# PARKPCB.net
KiCad netlist of a schematic drawn in EAGLE
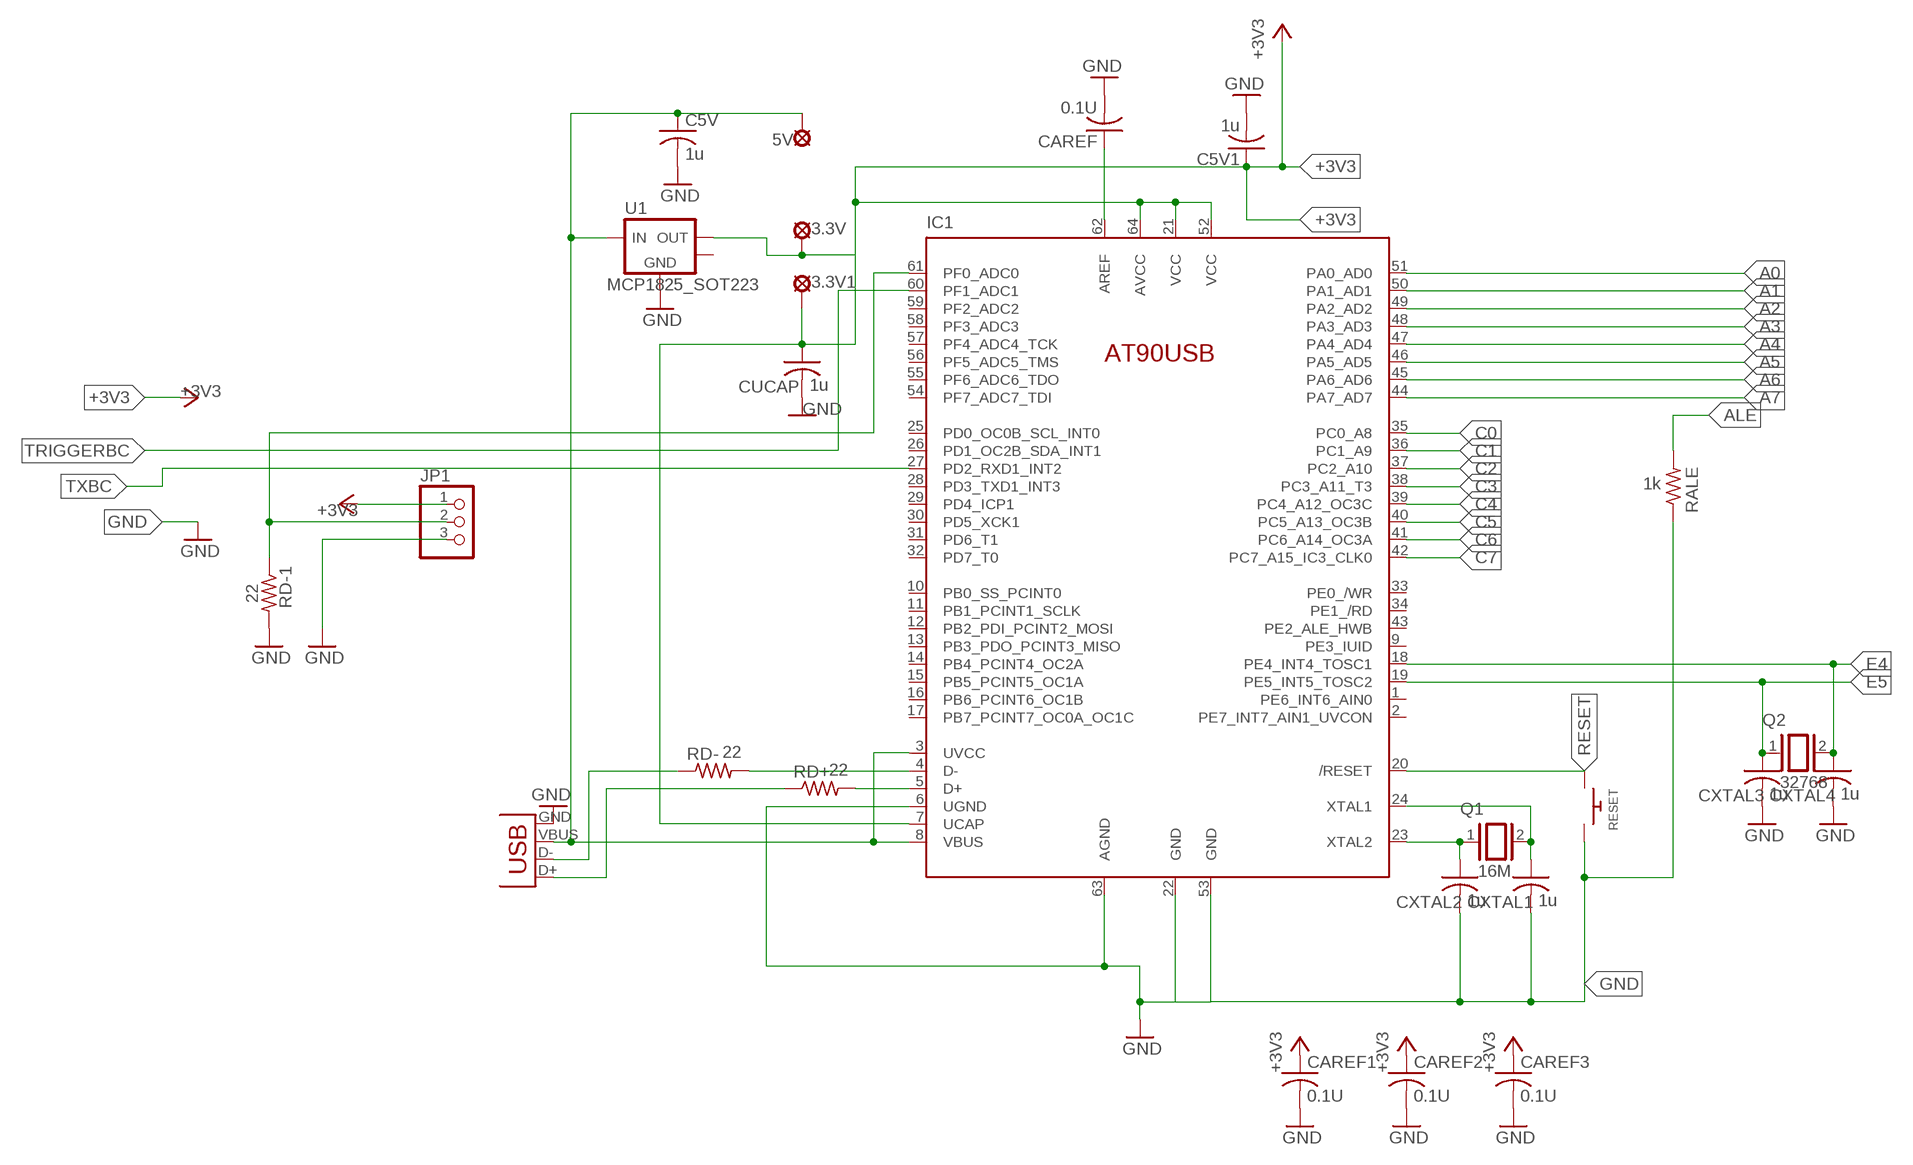
[diagram p0: schematic, sheet 1, part 1 of 2]
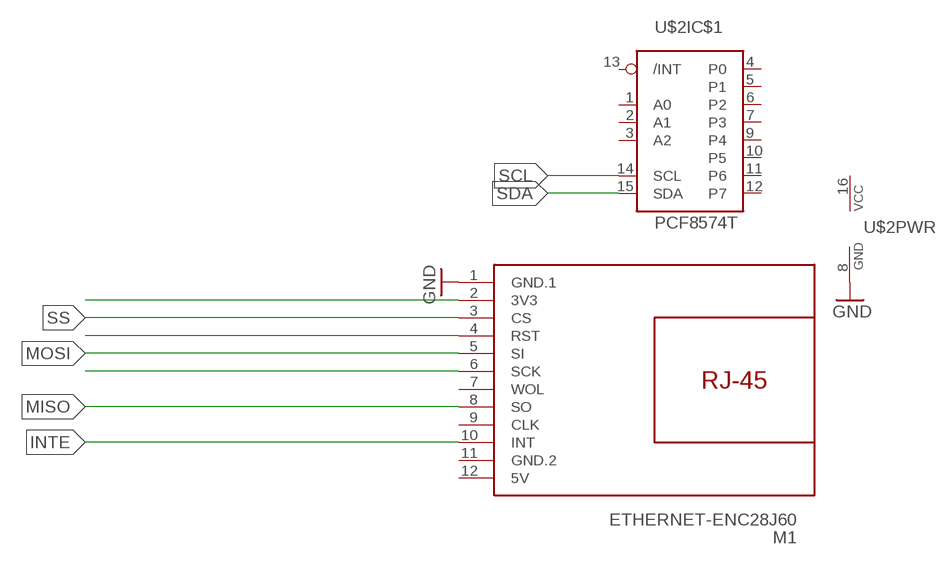
[diagram p1: schematic, sheet 1, part 2 of 2]

(export (version "E")
  (design (tool "Eeschema 10.0.6"))
  (components
    (comp (ref "3.3V")
      (value "LSP10")
      (footprint "eagle-import:LSP10")
      (libsource (lib "eagle-import") (part "LSP10"))
    )
    (comp (ref "3.3V1")
      (value "LSP10")
      (footprint "eagle-import:LSP10")
      (libsource (lib "eagle-import") (part "LSP10"))
    )
    (comp (ref "5V")
      (value "LSP10")
      (footprint "eagle-import:LSP10")
      (libsource (lib "eagle-import") (part "LSP10"))
    )
    (comp (ref "C5V")
      (value "1u")
      (footprint "eagle-import:C050-030X075")
      (libsource (lib "eagle-import") (part "C-US050-030X075"))
    )
    (comp (ref "C5V1")
      (value "1u")
      (footprint "eagle-import:C050-030X075")
      (libsource (lib "eagle-import") (part "C-US050-030X075"))
    )
    (comp (ref "CAREF")
      (value "0.1U")
      (footprint "eagle-import:C050-030X075")
      (libsource (lib "eagle-import") (part "C-US050-030X075"))
    )
    (comp (ref "CAREF1")
      (value "0.1U")
      (footprint "eagle-import:C050-030X075")
      (libsource (lib "eagle-import") (part "C-US050-030X075"))
    )
    (comp (ref "CAREF2")
      (value "0.1U")
      (footprint "eagle-import:C050-030X075")
      (libsource (lib "eagle-import") (part "C-US050-030X075"))
    )
    (comp (ref "CAREF3")
      (value "0.1U")
      (footprint "eagle-import:C050-030X075")
      (libsource (lib "eagle-import") (part "C-US050-030X075"))
    )
    (comp (ref "CUCAP")
      (value "1u")
      (footprint "eagle-import:C050-030X075")
      (libsource (lib "eagle-import") (part "C-US050-030X075"))
    )
    (comp (ref "CXTAL1")
      (value "1u")
      (footprint "eagle-import:C050-030X075")
      (libsource (lib "eagle-import") (part "C-US050-030X075"))
    )
    (comp (ref "CXTAL2")
      (value "1u")
      (footprint "eagle-import:C050-030X075")
      (libsource (lib "eagle-import") (part "C-US050-030X075"))
    )
    (comp (ref "CXTAL3")
      (value "1u")
      (footprint "eagle-import:C050-030X075")
      (libsource (lib "eagle-import") (part "C-US050-030X075"))
    )
    (comp (ref "CXTAL4")
      (value "1u")
      (footprint "eagle-import:C050-030X075")
      (libsource (lib "eagle-import") (part "C-US050-030X075"))
    )
    (comp (ref "IC1")
      (value "AT90USB-TQFP")
      (footprint "eagle-import:TQFP64")
      (libsource (lib "eagle-import") (part "AT90USB-TQFP"))
    )
    (comp (ref "JP1")
      (value "PINHD-1X3")
      (footprint "eagle-import:1X03")
      (libsource (lib "eagle-import") (part "PINHD-1X3"))
    )
    (comp (ref "M1")
      (value "ETHERNET-ENC28J60")
      (footprint "eagle-import:ETHERNET-ENC28J60")
      (libsource (lib "eagle-import") (part "ETHERNET-ENC28J60"))
    )
    (comp (ref "Q1")
      (value "16M")
      (footprint "eagle-import:QS")
      (libsource (lib "eagle-import") (part "XTAL/S"))
    )
    (comp (ref "Q2")
      (value "32768")
      (footprint "eagle-import:QS")
      (libsource (lib "eagle-import") (part "XTAL/S"))
    )
    (comp (ref "RALE")
      (value "1k")
      (footprint "eagle-import:0309_12")
      (libsource (lib "eagle-import") (part "R-US_0309/12"))
    )
    (comp (ref "RD+")
      (value "22")
      (footprint "eagle-import:0309_12")
      (libsource (lib "eagle-import") (part "R-US_0309/12"))
    )
    (comp (ref "RD-")
      (value "22")
      (footprint "eagle-import:0309_12")
      (libsource (lib "eagle-import") (part "R-US_0309/12"))
    )
    (comp (ref "RD-1")
      (value "22")
      (footprint "eagle-import:0309_12")
      (libsource (lib "eagle-import") (part "R-US_0309/12"))
    )
    (comp (ref "RESET")
      (value "SWITCH_PUSHBUTTONC&K_KSS")
      (footprint "eagle-import:BTN_CK_KSS")
      (libsource (lib "eagle-import") (part "SWITCH_PUSHBUTTONC&K_KSS"))
    )
    (comp (ref "U$2")
      (value "PCF8574T")
      (footprint "eagle-import:SO16")
      (libsource (lib "eagle-import") (part "PCF8574T"))
    )
    (comp (ref "U1")
      (value "MCP1825_SOT223")
      (footprint "eagle-import:SOT-223-3")
      (libsource (lib "eagle-import") (part "MCP1825_SOT223"))
    )
    (comp (ref "X1")
      (value "USB-MB-S")
      (footprint "eagle-import:USB-MB-S")
      (libsource (lib "eagle-import") (part "USB-MB-S"))
    )
  )
  (nets
    (net (code "1") (name "+3V3") (class "Default")
      (node (ref "3.3V") (pin "MP") (pinfunction "MP_MP") (pintype "passive"))
      (node (ref "3.3V1") (pin "MP") (pinfunction "MP_MP") (pintype "passive"))
      (node (ref "C5V1") (pin "1") (pinfunction "1_1") (pintype "passive"))
      (node (ref "CAREF1") (pin "1") (pinfunction "1_1") (pintype "passive"))
      (node (ref "CAREF2") (pin "1") (pinfunction "1_1") (pintype "passive"))
      (node (ref "CAREF3") (pin "1") (pinfunction "1_1") (pintype "passive"))
      (node (ref "CUCAP") (pin "1") (pinfunction "1_1") (pintype "passive"))
      (node (ref "IC1") (pin "21") (pinfunction "VCC_21") (pintype "power_in"))
      (node (ref "IC1") (pin "52") (pinfunction "VCC_52") (pintype "power_in"))
      (node (ref "IC1") (pin "64") (pinfunction "AVCC_64") (pintype "power_in"))
      (node (ref "IC1") (pin "7") (pinfunction "UCAP_7") (pintype "power_in"))
      (node (ref "JP1") (pin "1") (pinfunction "1_1") (pintype "passive"))
      (node (ref "U1") (pin "3") (pinfunction "VOUT_3") (pintype "power_in"))
    )
    (net (code "2") (name "/5V") (class "Default")
      (node (ref "M1") (pin "12") (pinfunction "5V_12") (pintype "power_in"))
    )
    (net (code "3") (name "/GND.2") (class "Default")
      (node (ref "M1") (pin "11") (pinfunction "GND.2_11") (pintype "power_in"))
    )
    (net (code "4") (name "/HEATSINK") (class "Default")
      (node (ref "U1") (pin "4") (pinfunction "HEATSINK_4") (pintype "power_in"))
    )
    (net (code "5") (name "/VCC") (class "Default")
      (node (ref "U$2") (pin "16") (pinfunction "VCC_16") (pintype "power_in"))
    )
    (net (code "6") (name "A0") (class "Default")
      (node (ref "IC1") (pin "51") (pinfunction "PA0_AD0_51") (pintype "bidirectional"))
    )
    (net (code "7") (name "A1") (class "Default")
      (node (ref "IC1") (pin "50") (pinfunction "PA1_AD1_50") (pintype "bidirectional"))
    )
    (net (code "8") (name "A2") (class "Default")
      (node (ref "IC1") (pin "49") (pinfunction "PA2_AD2_49") (pintype "bidirectional"))
    )
    (net (code "9") (name "A3") (class "Default")
      (node (ref "IC1") (pin "48") (pinfunction "PA3_AD3_48") (pintype "bidirectional"))
    )
    (net (code "10") (name "A4") (class "Default")
      (node (ref "IC1") (pin "47") (pinfunction "PA4_AD4_47") (pintype "bidirectional"))
    )
    (net (code "11") (name "A5") (class "Default")
      (node (ref "IC1") (pin "46") (pinfunction "PA5_AD5_46") (pintype "bidirectional"))
    )
    (net (code "12") (name "A6") (class "Default")
      (node (ref "IC1") (pin "45") (pinfunction "PA6_AD6_45") (pintype "bidirectional"))
    )
    (net (code "13") (name "A7") (class "Default")
      (node (ref "IC1") (pin "44") (pinfunction "PA7_AD7_44") (pintype "bidirectional"))
    )
    (net (code "14") (name "ALE") (class "Default")
      (node (ref "RALE") (pin "2") (pinfunction "2_2") (pintype "passive"))
    )
    (net (code "15") (name "C0") (class "Default")
      (node (ref "IC1") (pin "35") (pinfunction "PC0_A8_35") (pintype "bidirectional"))
    )
    (net (code "16") (name "C1") (class "Default")
      (node (ref "IC1") (pin "36") (pinfunction "PC1_A9_36") (pintype "bidirectional"))
    )
    (net (code "17") (name "C2") (class "Default")
      (node (ref "IC1") (pin "37") (pinfunction "PC2_A10_37") (pintype "bidirectional"))
    )
    (net (code "18") (name "C3") (class "Default")
      (node (ref "IC1") (pin "38") (pinfunction "PC3_A11_T3_38") (pintype "bidirectional"))
    )
    (net (code "19") (name "C4") (class "Default")
      (node (ref "IC1") (pin "39") (pinfunction "PC4_A12_OC3C_39") (pintype "bidirectional"))
    )
    (net (code "20") (name "C5") (class "Default")
      (node (ref "IC1") (pin "40") (pinfunction "PC5_A13_OC3B_40") (pintype "bidirectional"))
    )
    (net (code "21") (name "C6") (class "Default")
      (node (ref "IC1") (pin "41") (pinfunction "PC6_A14_OC3A_41") (pintype "bidirectional"))
    )
    (net (code "22") (name "C7") (class "Default")
      (node (ref "IC1") (pin "42") (pinfunction "PC7_A15_IC3_CLK0_42") (pintype "bidirectional"))
    )
    (net (code "23") (name "E4") (class "Default")
      (node (ref "CXTAL4") (pin "1") (pinfunction "1_1") (pintype "passive"))
      (node (ref "IC1") (pin "18") (pinfunction "PE4_INT4_TOSC1_18") (pintype "bidirectional"))
      (node (ref "Q2") (pin "2") (pinfunction "2_2") (pintype "passive"))
    )
    (net (code "24") (name "E5") (class "Default")
      (node (ref "CXTAL3") (pin "1") (pinfunction "1_1") (pintype "passive"))
      (node (ref "IC1") (pin "19") (pinfunction "PE5_INT5_TOSC2_19") (pintype "bidirectional"))
      (node (ref "Q2") (pin "1") (pinfunction "1_1") (pintype "passive"))
    )
    (net (code "25") (name "GND") (class "Default")
      (node (ref "C5V") (pin "2") (pinfunction "2_2") (pintype "passive"))
      (node (ref "C5V1") (pin "2") (pinfunction "2_2") (pintype "passive"))
      (node (ref "CAREF") (pin "2") (pinfunction "2_2") (pintype "passive"))
      (node (ref "CAREF1") (pin "2") (pinfunction "2_2") (pintype "passive"))
      (node (ref "CAREF2") (pin "2") (pinfunction "2_2") (pintype "passive"))
      (node (ref "CAREF3") (pin "2") (pinfunction "2_2") (pintype "passive"))
      (node (ref "CUCAP") (pin "2") (pinfunction "2_2") (pintype "passive"))
      (node (ref "CXTAL1") (pin "2") (pinfunction "2_2") (pintype "passive"))
      (node (ref "CXTAL2") (pin "2") (pinfunction "2_2") (pintype "passive"))
      (node (ref "CXTAL3") (pin "2") (pinfunction "2_2") (pintype "passive"))
      (node (ref "CXTAL4") (pin "2") (pinfunction "2_2") (pintype "passive"))
      (node (ref "IC1") (pin "22") (pinfunction "GND_22") (pintype "power_in"))
      (node (ref "IC1") (pin "53") (pinfunction "GND_53") (pintype "power_in"))
      (node (ref "IC1") (pin "6") (pinfunction "UGND_6") (pintype "power_in"))
      (node (ref "IC1") (pin "63") (pinfunction "AGND_63") (pintype "power_in"))
      (node (ref "JP1") (pin "3") (pinfunction "3_3") (pintype "passive"))
      (node (ref "M1") (pin "1") (pinfunction "GND.1_1") (pintype "power_in"))
      (node (ref "RALE") (pin "1") (pinfunction "1_1") (pintype "passive"))
      (node (ref "RD-1") (pin "2") (pinfunction "2_2") (pintype "passive"))
      (node (ref "RESET") (pin "P$2") (pinfunction "P$2_P$2") (pintype "passive"))
      (node (ref "U$2") (pin "8") (pinfunction "GND_8") (pintype "power_in"))
      (node (ref "U1") (pin "2") (pinfunction "GND_2") (pintype "power_in"))
      (node (ref "X1") (pin "GND") (pinfunction "GND_GND") (pintype "bidirectional"))
    )
    (net (code "26") (name "INTE") (class "Default")
      (node (ref "M1") (pin "10") (pinfunction "INT_10") (pintype "bidirectional"))
    )
    (net (code "27") (name "MISO") (class "Default")
      (node (ref "M1") (pin "8") (pinfunction "SO_8") (pintype "bidirectional"))
    )
    (net (code "28") (name "MOSI") (class "Default")
      (node (ref "M1") (pin "5") (pinfunction "SI_5") (pintype "bidirectional"))
    )
    (net (code "29") (name "Net-(IC1-AREF)") (class "Default")
      (node (ref "CAREF") (pin "1") (pinfunction "1_1") (pintype "passive"))
      (node (ref "IC1") (pin "62") (pinfunction "AREF_62") (pintype "power_in"))
    )
    (net (code "30") (name "Net-(IC1-D+)") (class "Default")
      (node (ref "IC1") (pin "5") (pinfunction "D+_5") (pintype "bidirectional"))
      (node (ref "RD+") (pin "2") (pinfunction "2_2") (pintype "passive"))
    )
    (net (code "31") (name "Net-(IC1-D-)") (class "Default")
      (node (ref "IC1") (pin "4") (pinfunction "D-_4") (pintype "bidirectional"))
      (node (ref "RD-") (pin "2") (pinfunction "2_2") (pintype "passive"))
    )
    (net (code "32") (name "Net-(IC1-PF0_ADC0)") (class "Default")
      (node (ref "IC1") (pin "61") (pinfunction "PF0_ADC0_61") (pintype "bidirectional"))
      (node (ref "JP1") (pin "2") (pinfunction "2_2") (pintype "passive"))
      (node (ref "RD-1") (pin "1") (pinfunction "1_1") (pintype "passive"))
    )
    (net (code "33") (name "Net-(IC1-UVCC)") (class "Default")
      (node (ref "5V") (pin "MP") (pinfunction "MP_MP") (pintype "passive"))
      (node (ref "C5V") (pin "1") (pinfunction "1_1") (pintype "passive"))
      (node (ref "IC1") (pin "3") (pinfunction "UVCC_3") (pintype "power_in"))
      (node (ref "IC1") (pin "8") (pinfunction "VBUS_8") (pintype "bidirectional"))
      (node (ref "U1") (pin "1") (pinfunction "VIN_1") (pintype "power_in"))
      (node (ref "X1") (pin "VBUS") (pinfunction "VBUS_VBUS") (pintype "bidirectional"))
    )
    (net (code "34") (name "Net-(IC1-XTAL1)") (class "Default")
      (node (ref "CXTAL1") (pin "1") (pinfunction "1_1") (pintype "passive"))
      (node (ref "IC1") (pin "24") (pinfunction "XTAL1_24") (pintype "passive"))
      (node (ref "Q1") (pin "2") (pinfunction "2_2") (pintype "passive"))
    )
    (net (code "35") (name "Net-(IC1-XTAL2)") (class "Default")
      (node (ref "CXTAL2") (pin "1") (pinfunction "1_1") (pintype "passive"))
      (node (ref "IC1") (pin "23") (pinfunction "XTAL2_23") (pintype "passive"))
      (node (ref "Q1") (pin "1") (pinfunction "1_1") (pintype "passive"))
    )
    (net (code "36") (name "Net-(RD+-Pad1)") (class "Default")
      (node (ref "RD+") (pin "1") (pinfunction "1_1") (pintype "passive"))
      (node (ref "X1") (pin "D+") (pinfunction "D+_D+") (pintype "bidirectional"))
    )
    (net (code "37") (name "Net-(RD--Pad1)") (class "Default")
      (node (ref "RD-") (pin "1") (pinfunction "1_1") (pintype "passive"))
      (node (ref "X1") (pin "D-") (pinfunction "D-_D-") (pintype "bidirectional"))
    )
    (net (code "38") (name "RESET") (class "Default")
      (node (ref "IC1") (pin "20") (pinfunction "/RESET_20") (pintype "bidirectional"))
      (node (ref "RESET") (pin "P$1") (pinfunction "P$1_P$1") (pintype "passive"))
    )
    (net (code "39") (name "SCL") (class "Default")
      (node (ref "U$2") (pin "14") (pinfunction "SCL_14") (pintype "input"))
    )
    (net (code "40") (name "SDA") (class "Default")
      (node (ref "U$2") (pin "15") (pinfunction "SDA_15") (pintype "bidirectional"))
    )
    (net (code "41") (name "SS") (class "Default")
      (node (ref "M1") (pin "3") (pinfunction "CS_3") (pintype "bidirectional"))
    )
    (net (code "42") (name "TRIGGERBC") (class "Default")
      (node (ref "IC1") (pin "60") (pinfunction "PF1_ADC1_60") (pintype "bidirectional"))
    )
    (net (code "43") (name "TXBC") (class "Default")
      (node (ref "IC1") (pin "27") (pinfunction "PD2_RXD1_INT2_27") (pintype "bidirectional"))
    )
    (net (code "44") (name "unconnected-(IC1-PB0_SS_PCINT0-Pad10)") (class "Default")
      (node (ref "IC1") (pin "10") (pinfunction "PB0_SS_PCINT0_10") (pintype "bidirectional"))
    )
    (net (code "45") (name "unconnected-(IC1-PB1_PCINT1_SCLK-Pad11)") (class "Default")
      (node (ref "IC1") (pin "11") (pinfunction "PB1_PCINT1_SCLK_11") (pintype "bidirectional"))
    )
    (net (code "46") (name "unconnected-(IC1-PB2_PDI_PCINT2_MOSI-Pad12)") (class "Default")
      (node (ref "IC1") (pin "12") (pinfunction "PB2_PDI_PCINT2_MOSI_12") (pintype "bidirectional"))
    )
    (net (code "47") (name "unconnected-(IC1-PB3_PDO_PCINT3_MISO-Pad13)") (class "Default")
      (node (ref "IC1") (pin "13") (pinfunction "PB3_PDO_PCINT3_MISO_13") (pintype "bidirectional"))
    )
    (net (code "48") (name "unconnected-(IC1-PB4_PCINT4_OC2A-Pad14)") (class "Default")
      (node (ref "IC1") (pin "14") (pinfunction "PB4_PCINT4_OC2A_14") (pintype "bidirectional"))
    )
    (net (code "49") (name "unconnected-(IC1-PB5_PCINT5_OC1A-Pad15)") (class "Default")
      (node (ref "IC1") (pin "15") (pinfunction "PB5_PCINT5_OC1A_15") (pintype "bidirectional"))
    )
    (net (code "50") (name "unconnected-(IC1-PB6_PCINT6_OC1B-Pad16)") (class "Default")
      (node (ref "IC1") (pin "16") (pinfunction "PB6_PCINT6_OC1B_16") (pintype "bidirectional"))
    )
    (net (code "51") (name "unconnected-(IC1-PB7_PCINT7_OC0A_OC1C-Pad17)") (class "Default")
      (node (ref "IC1") (pin "17") (pinfunction "PB7_PCINT7_OC0A_OC1C_17") (pintype "bidirectional"))
    )
    (net (code "52") (name "unconnected-(IC1-PD0_OC0B_SCL_INT0-Pad25)") (class "Default")
      (node (ref "IC1") (pin "25") (pinfunction "PD0_OC0B_SCL_INT0_25") (pintype "bidirectional"))
    )
    (net (code "53") (name "unconnected-(IC1-PD1_OC2B_SDA_INT1-Pad26)") (class "Default")
      (node (ref "IC1") (pin "26") (pinfunction "PD1_OC2B_SDA_INT1_26") (pintype "bidirectional"))
    )
    (net (code "54") (name "unconnected-(IC1-PD3_TXD1_INT3-Pad28)") (class "Default")
      (node (ref "IC1") (pin "28") (pinfunction "PD3_TXD1_INT3_28") (pintype "bidirectional"))
    )
    (net (code "55") (name "unconnected-(IC1-PD4_ICP1-Pad29)") (class "Default")
      (node (ref "IC1") (pin "29") (pinfunction "PD4_ICP1_29") (pintype "bidirectional"))
    )
    (net (code "56") (name "unconnected-(IC1-PD5_XCK1-Pad30)") (class "Default")
      (node (ref "IC1") (pin "30") (pinfunction "PD5_XCK1_30") (pintype "bidirectional"))
    )
    (net (code "57") (name "unconnected-(IC1-PD6_T1-Pad31)") (class "Default")
      (node (ref "IC1") (pin "31") (pinfunction "PD6_T1_31") (pintype "bidirectional"))
    )
    (net (code "58") (name "unconnected-(IC1-PD7_T0-Pad32)") (class "Default")
      (node (ref "IC1") (pin "32") (pinfunction "PD7_T0_32") (pintype "bidirectional"))
    )
    (net (code "59") (name "unconnected-(IC1-PE0_{slash}WR-Pad33)") (class "Default")
      (node (ref "IC1") (pin "33") (pinfunction "PE0_/WR_33") (pintype "bidirectional"))
    )
    (net (code "60") (name "unconnected-(IC1-PE1_{slash}RD-Pad34)") (class "Default")
      (node (ref "IC1") (pin "34") (pinfunction "PE1_/RD_34") (pintype "bidirectional"))
    )
    (net (code "61") (name "unconnected-(IC1-PE2_ALE_HWB-Pad43)") (class "Default")
      (node (ref "IC1") (pin "43") (pinfunction "PE2_ALE_HWB_43") (pintype "bidirectional"))
    )
    (net (code "62") (name "unconnected-(IC1-PE3_IUID-Pad9)") (class "Default")
      (node (ref "IC1") (pin "9") (pinfunction "PE3_IUID_9") (pintype "bidirectional"))
    )
    (net (code "63") (name "unconnected-(IC1-PE6_INT6_AIN0-Pad1)") (class "Default")
      (node (ref "IC1") (pin "1") (pinfunction "PE6_INT6_AIN0_1") (pintype "bidirectional"))
    )
    (net (code "64") (name "unconnected-(IC1-PE7_INT7_AIN1_UVCON-Pad2)") (class "Default")
      (node (ref "IC1") (pin "2") (pinfunction "PE7_INT7_AIN1_UVCON_2") (pintype "bidirectional"))
    )
    (net (code "65") (name "unconnected-(IC1-PF2_ADC2-Pad59)") (class "Default")
      (node (ref "IC1") (pin "59") (pinfunction "PF2_ADC2_59") (pintype "bidirectional"))
    )
    (net (code "66") (name "unconnected-(IC1-PF3_ADC3-Pad58)") (class "Default")
      (node (ref "IC1") (pin "58") (pinfunction "PF3_ADC3_58") (pintype "bidirectional"))
    )
    (net (code "67") (name "unconnected-(IC1-PF4_ADC4_TCK-Pad57)") (class "Default")
      (node (ref "IC1") (pin "57") (pinfunction "PF4_ADC4_TCK_57") (pintype "bidirectional"))
    )
    (net (code "68") (name "unconnected-(IC1-PF5_ADC5_TMS-Pad56)") (class "Default")
      (node (ref "IC1") (pin "56") (pinfunction "PF5_ADC5_TMS_56") (pintype "bidirectional"))
    )
    (net (code "69") (name "unconnected-(IC1-PF6_ADC6_TDO-Pad55)") (class "Default")
      (node (ref "IC1") (pin "55") (pinfunction "PF6_ADC6_TDO_55") (pintype "bidirectional"))
    )
    (net (code "70") (name "unconnected-(IC1-PF7_ADC7_TDI-Pad54)") (class "Default")
      (node (ref "IC1") (pin "54") (pinfunction "PF7_ADC7_TDI_54") (pintype "bidirectional"))
    )
    (net (code "71") (name "unconnected-(M1-3V3-Pad2)") (class "Default")
      (node (ref "M1") (pin "2") (pinfunction "3V3_2") (pintype "power_in"))
    )
    (net (code "72") (name "unconnected-(M1-CLK-Pad9)") (class "Default")
      (node (ref "M1") (pin "9") (pinfunction "CLK_9") (pintype "bidirectional"))
    )
    (net (code "73") (name "unconnected-(M1-RST-Pad4)") (class "Default")
      (node (ref "M1") (pin "4") (pinfunction "RST_4") (pintype "bidirectional"))
    )
    (net (code "74") (name "unconnected-(M1-SCK-Pad6)") (class "Default")
      (node (ref "M1") (pin "6") (pinfunction "SCK_6") (pintype "bidirectional"))
    )
    (net (code "75") (name "unconnected-(M1-WOL-Pad7)") (class "Default")
      (node (ref "M1") (pin "7") (pinfunction "WOL_7") (pintype "bidirectional"))
    )
    (net (code "76") (name "unconnected-(U$2A-A0-Pad1)") (class "Default")
      (node (ref "U$2") (pin "1") (pinfunction "A0_1") (pintype "input"))
    )
    (net (code "77") (name "unconnected-(U$2A-A1-Pad2)") (class "Default")
      (node (ref "U$2") (pin "2") (pinfunction "A1_2") (pintype "input"))
    )
    (net (code "78") (name "unconnected-(U$2A-A2-Pad3)") (class "Default")
      (node (ref "U$2") (pin "3") (pinfunction "A2_3") (pintype "input"))
    )
    (net (code "79") (name "unconnected-(U$2A-P0-Pad4)") (class "Default")
      (node (ref "U$2") (pin "4") (pinfunction "P0_4") (pintype "bidirectional"))
    )
    (net (code "80") (name "unconnected-(U$2A-P1-Pad5)") (class "Default")
      (node (ref "U$2") (pin "5") (pinfunction "P1_5") (pintype "bidirectional"))
    )
    (net (code "81") (name "unconnected-(U$2A-P2-Pad6)") (class "Default")
      (node (ref "U$2") (pin "6") (pinfunction "P2_6") (pintype "bidirectional"))
    )
    (net (code "82") (name "unconnected-(U$2A-P3-Pad7)") (class "Default")
      (node (ref "U$2") (pin "7") (pinfunction "P3_7") (pintype "bidirectional"))
    )
    (net (code "83") (name "unconnected-(U$2A-P4-Pad9)") (class "Default")
      (node (ref "U$2") (pin "9") (pinfunction "P4_9") (pintype "bidirectional"))
    )
    (net (code "84") (name "unconnected-(U$2A-P5-Pad10)") (class "Default")
      (node (ref "U$2") (pin "10") (pinfunction "P5_10") (pintype "bidirectional"))
    )
    (net (code "85") (name "unconnected-(U$2A-P6-Pad11)") (class "Default")
      (node (ref "U$2") (pin "11") (pinfunction "P6_11") (pintype "bidirectional"))
    )
    (net (code "86") (name "unconnected-(U$2A-P7-Pad12)") (class "Default")
      (node (ref "U$2") (pin "12") (pinfunction "P7_12") (pintype "bidirectional"))
    )
    (net (code "87") (name "unconnected-(U$2A-{slash}INT-Pad13)") (class "Default")
      (node (ref "U$2") (pin "13") (pinfunction "/INT_13") (pintype "output"))
    )
  )
)
